# edison_misc.net
KiCad netlist of a schematic drawn in Altium Designer
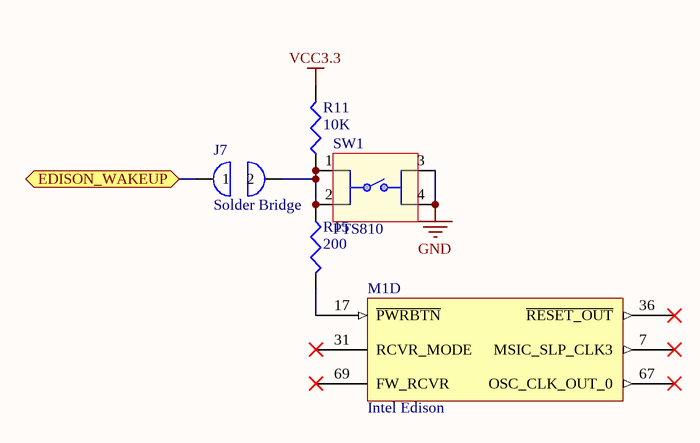
[diagram p0: edison_misc.SchDoc]

(export (version "E")
  (design (tool "Eeschema 10.0.6"))
  (components
    (comp (ref "J7")
      (value "Solder Bridge")
      (footprint "SolderBridge")
      (libsource (lib "connectors") (part "SolderBridge"))
    )
    (comp (ref "M1")
      (value "Intel Edison")
      (footprint "Intel Edison mating")
      (libsource (lib "edison") (part "Intel Edison"))
    )
    (comp (ref "R11")
      (value "10K")
      (footprint "0402")
      (description "Chip resistor, 10K, 0402 package")
      (fields (field (name "TOLERANCE") "1%") (field (name "POWER") "1/16 W"))
      (libsource (lib "rlc") (part "R_10K_0402"))
    )
    (comp (ref "R15")
      (value "200")
      (footprint "0402")
      (description "Chip resistor, 200, 0402 package")
      (fields (field (name "TOLERANCE") "1%") (field (name "POWER") "1/16 W"))
      (libsource (lib "rlc") (part "R_200_0402"))
    )
    (comp (ref "SW1")
      (value "PTS810")
      (footprint "PTS810")
      (description "Tactile Switches")
      (libsource (lib "switches") (part "PTS810"))
    )
  )
  (nets
    (net (code "1") (name "/EDISON_WAKEUP") (class "Default")
      (node (ref "J7") (pin "1") (pinfunction "1_1") (pintype "passive"))
    )
    (net (code "2") (name "GND") (class "Default")
      (node (ref "SW1") (pin "3") (pinfunction "3_3") (pintype "passive"))
      (node (ref "SW1") (pin "4") (pinfunction "4_4") (pintype "passive"))
    )
    (net (code "3") (name "Net-(J7-Pad2)") (class "Default")
      (node (ref "J7") (pin "2") (pinfunction "2_2") (pintype "passive"))
      (node (ref "R11") (pin "2") (pintype "passive"))
      (node (ref "R15") (pin "2") (pintype "passive"))
      (node (ref "SW1") (pin "1") (pinfunction "1_1") (pintype "passive"))
      (node (ref "SW1") (pin "2") (pinfunction "2_2") (pintype "passive"))
    )
    (net (code "4") (name "Net-(M1D-~{PWRBTN})") (class "Default")
      (node (ref "M1") (pin "17") (pinfunction "~{PWRBTN}_17") (pintype "input"))
      (node (ref "R15") (pin "1") (pintype "passive"))
    )
    (net (code "5") (name "VCC3.3") (class "Default") (node (ref "R11") (pin "1") (pintype "passive")))
    (net (code "6") (name "unconnected-(M1D-FW_RCVR-Pad69)") (class "Default")
      (node (ref "M1") (pin "69") (pinfunction "FW_RCVR_69") (pintype "passive+no_connect"))
    )
    (net (code "7") (name "unconnected-(M1D-MSIC_SLP_CLK3-Pad7)") (class "Default")
      (node (ref "M1") (pin "7") (pinfunction "MSIC_SLP_CLK3_7") (pintype "output+no_connect"))
    )
    (net (code "8") (name "unconnected-(M1D-OSC_CLK_OUT_0-Pad67)") (class "Default")
      (node (ref "M1") (pin "67") (pinfunction "OSC_CLK_OUT_0_67") (pintype "output+no_connect"))
    )
    (net (code "9") (name "unconnected-(M1D-RCVR_MODE-Pad31)") (class "Default")
      (node (ref "M1") (pin "31") (pinfunction "RCVR_MODE_31") (pintype "passive+no_connect"))
    )
    (net (code "10") (name "unconnected-(M1D-~{RESET_OUT}-Pad36)") (class "Default")
      (node (ref "M1") (pin "36") (pinfunction "~{RESET_OUT}_36") (pintype "output+no_connect"))
    )
  )
)
